# H_bridge.net
KiCad netlist of a schematic drawn in Altium Designer
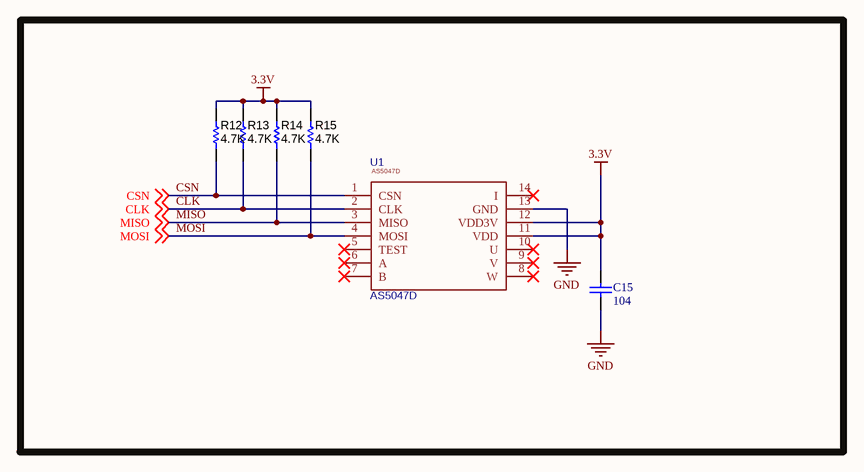
[diagram p0: H_bridge.SchDoc]

(export (version "E")
  (design (tool "Eeschema 10.0.6"))
  (components
    (comp (ref "C15")
      (value "104")
      (footprint "TU_SMD_0805")
      (libsource (lib "MH_DA_THU_VIEN_16122016") (part "TU_SMD_0805_MH"))
    )
    (comp (ref "R12")
      (value "4.7K")
      (footprint "0805_HV")
      (description "RES, 100, 1%, 0.1 W, 0402")
      (fields
        (field (name "PARTNUMBER") "ERJ-2RKF1000X")
        (field (name "MANUFACTURER") "Panasonic")
        (field (name "PUBLISHER") "Texas Instruments")
      )
      (libsource (lib "mySch") (part "R nho"))
    )
    (comp (ref "R13")
      (value "4.7K")
      (footprint "0805_HV")
      (description "RES, 100, 1%, 0.1 W, 0402")
      (fields
        (field (name "PARTNUMBER") "ERJ-2RKF1000X")
        (field (name "MANUFACTURER") "Panasonic")
        (field (name "PUBLISHER") "Texas Instruments")
      )
      (libsource (lib "mySch") (part "R nho"))
    )
    (comp (ref "R14")
      (value "4.7K")
      (footprint "0805_HV")
      (description "RES, 100, 1%, 0.1 W, 0402")
      (fields
        (field (name "PARTNUMBER") "ERJ-2RKF1000X")
        (field (name "MANUFACTURER") "Panasonic")
        (field (name "PUBLISHER") "Texas Instruments")
      )
      (libsource (lib "mySch") (part "R nho"))
    )
    (comp (ref "R15")
      (value "4.7K")
      (footprint "0805_HV")
      (description "RES, 100, 1%, 0.1 W, 0402")
      (fields
        (field (name "PARTNUMBER") "ERJ-2RKF1000X")
        (field (name "MANUFACTURER") "Panasonic")
        (field (name "PUBLISHER") "Texas Instruments")
      )
      (libsource (lib "mySch") (part "R nho"))
    )
    (comp (ref "U1")
      (value "AS5047D")
      (footprint "TSSOP14")
      (fields (field (name "BOM_MANUFACTURER PART") "?"))
      (libsource (lib "mySch") (part "AS5047D"))
    )
  )
  (nets
    (net (code "1") (name "3.3V") (class "Default")
      (node (ref "C15") (pin "2") (pinfunction "2_2") (pintype "passive"))
      (node (ref "R12") (pin "2") (pinfunction "2_2") (pintype "passive"))
      (node (ref "R13") (pin "2") (pinfunction "2_2") (pintype "passive"))
      (node (ref "R14") (pin "2") (pinfunction "2_2") (pintype "passive"))
      (node (ref "R15") (pin "2") (pinfunction "2_2") (pintype "passive"))
      (node (ref "U1") (pin "11") (pinfunction "VDD_11") (pintype "passive"))
      (node (ref "U1") (pin "12") (pinfunction "VDD3V_12") (pintype "passive"))
    )
    (net (code "2") (name "CLK") (class "Default")
      (node (ref "R13") (pin "1") (pinfunction "1_1") (pintype "passive"))
      (node (ref "U1") (pin "2") (pinfunction "CLK_2") (pintype "passive"))
    )
    (net (code "3") (name "CSN") (class "Default")
      (node (ref "R12") (pin "1") (pinfunction "1_1") (pintype "passive"))
      (node (ref "U1") (pin "1") (pinfunction "CSN_1") (pintype "passive"))
    )
    (net (code "4") (name "GND") (class "Default")
      (node (ref "C15") (pin "1") (pinfunction "1_1") (pintype "passive"))
      (node (ref "U1") (pin "13") (pinfunction "GND_13") (pintype "passive"))
    )
    (net (code "5") (name "MISO") (class "Default")
      (node (ref "R14") (pin "1") (pinfunction "1_1") (pintype "passive"))
      (node (ref "U1") (pin "3") (pinfunction "MISO_3") (pintype "passive"))
    )
    (net (code "6") (name "MOSI") (class "Default")
      (node (ref "R15") (pin "1") (pinfunction "1_1") (pintype "passive"))
      (node (ref "U1") (pin "4") (pinfunction "MOSI_4") (pintype "passive"))
    )
    (net (code "7") (name "unconnected-(U1-A-Pad6)") (class "Default")
      (node (ref "U1") (pin "6") (pinfunction "A_6") (pintype "passive+no_connect"))
    )
    (net (code "8") (name "unconnected-(U1-B-Pad7)") (class "Default")
      (node (ref "U1") (pin "7") (pinfunction "B_7") (pintype "passive+no_connect"))
    )
    (net (code "9") (name "unconnected-(U1-I-Pad14)") (class "Default")
      (node (ref "U1") (pin "14") (pinfunction "I_14") (pintype "passive+no_connect"))
    )
    (net (code "10") (name "unconnected-(U1-TEST-Pad5)") (class "Default")
      (node (ref "U1") (pin "5") (pinfunction "TEST_5") (pintype "passive+no_connect"))
    )
    (net (code "11") (name "unconnected-(U1-U-Pad10)") (class "Default")
      (node (ref "U1") (pin "10") (pinfunction "U_10") (pintype "passive+no_connect"))
    )
    (net (code "12") (name "unconnected-(U1-V-Pad9)") (class "Default")
      (node (ref "U1") (pin "9") (pinfunction "V_9") (pintype "passive+no_connect"))
    )
    (net (code "13") (name "unconnected-(U1-W-Pad8)") (class "Default")
      (node (ref "U1") (pin "8") (pinfunction "W_8") (pintype "passive+no_connect"))
    )
  )
)
